# Logturtle_TX_Toplevel.net
KiCad netlist of a schematic drawn in Altium Designer
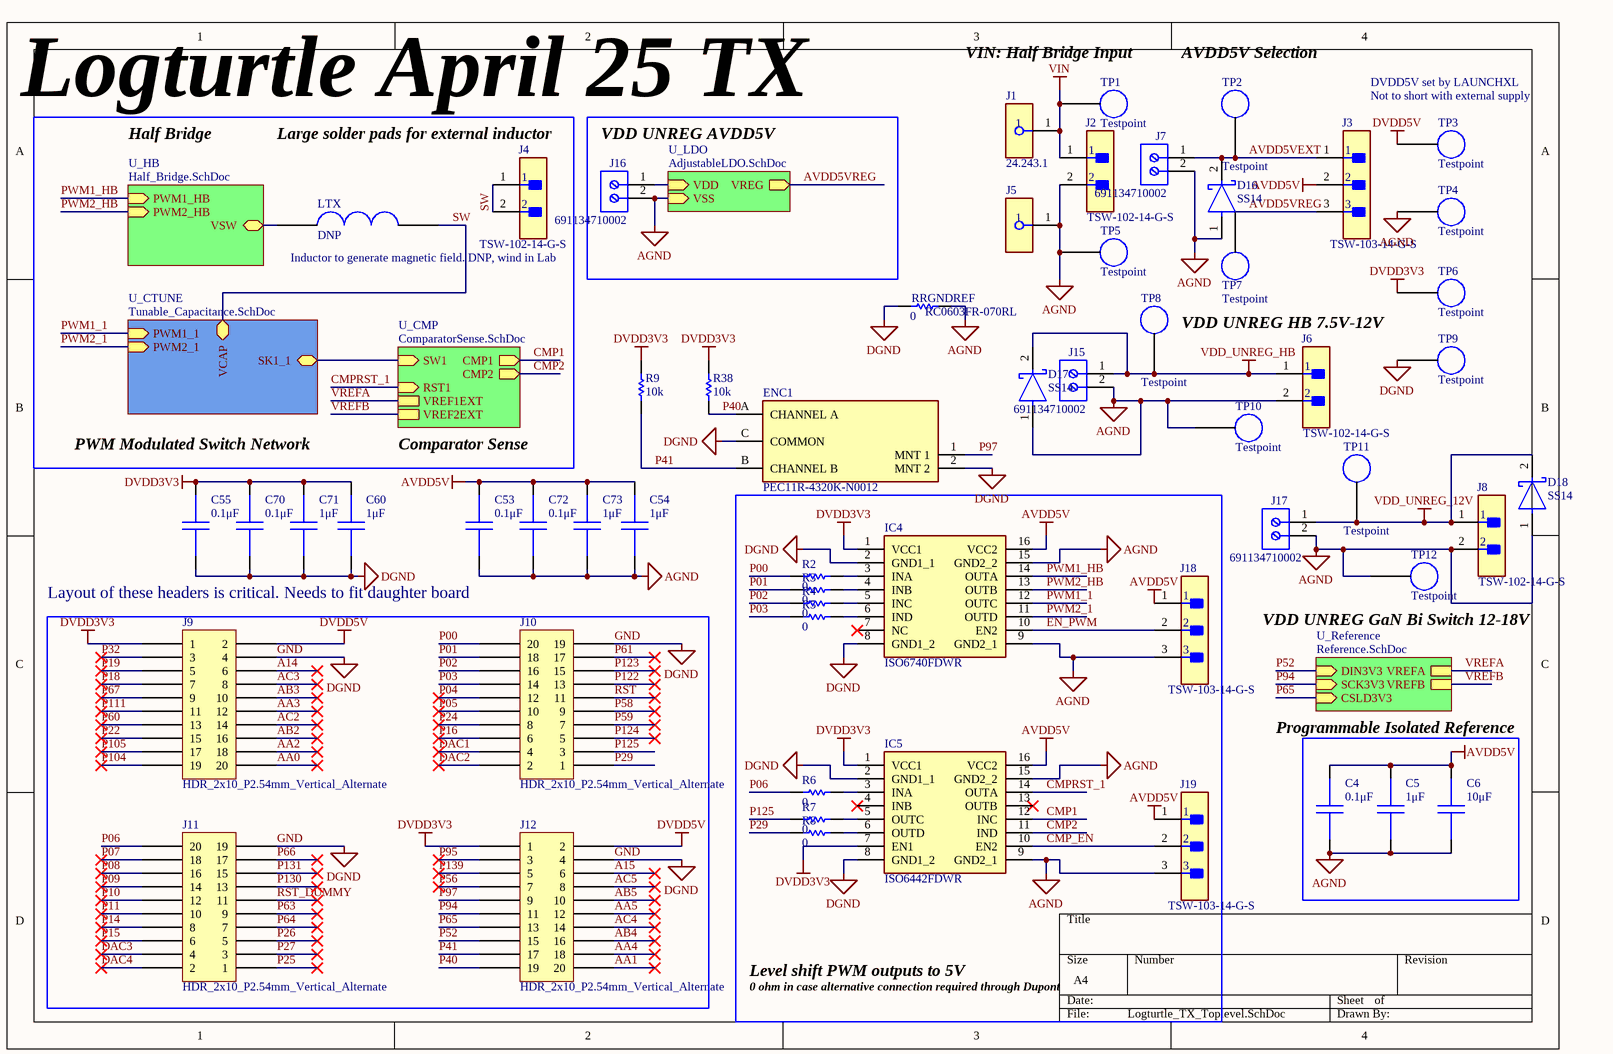
[diagram p0: Logturtle_TX_Toplevel.SchDoc]

(export (version "E")
  (design (tool "Eeschema 10.0.6"))
  (components
    (comp (ref "C4")
      (value "0.1μF")
      (footprint "CAPC1608X90N")
      (fields
        (field (name "MANUFACTURER") "Yageo")
        (field (name "MANUFACTURER PART NUMBER") "CC0603KRX7R7BB104")
      )
      (libsource (lib "LOGTURTLE_APR_25_TX") (part "CC0603KRX7R7BB104"))
    )
    (comp (ref "C5")
      (value "1μF")
      (footprint "CAPC1608X09N")
      (fields
        (field (name "MANUFACTURER") "Yageo")
        (field (name "MANUFACTURER PART NUMBER") "CC0603KRX7R7BB105")
      )
      (libsource (lib "LOGTURTLE_APR_25_TX") (part "CC0603KRX7R7BB105"))
    )
    (comp (ref "C6")
      (value "10μF")
      (footprint "CAPC2012X14N")
      (fields
        (field (name "MANUFACTURER") "Murata")
        (field (name "MANUFACTURER PART NUMBER") "GRM21BZ71E106KE15L")
        (field (name "TOLERANCE") "10%")
      )
      (libsource (lib "LOGTURTLE_APR_25_TX") (part "GRM21BZ71E106KE15L"))
    )
    (comp (ref "C53")
      (value "0.1μF")
      (footprint "CAPC1608X90N")
      (fields
        (field (name "MANUFACTURER") "Yageo")
        (field (name "MANUFACTURER PART NUMBER") "CC0603KRX7R7BB104")
      )
      (libsource (lib "LOGTURTLE_APR_25_TX") (part "CC0603KRX7R7BB104"))
    )
    (comp (ref "C54")
      (value "1μF")
      (footprint "CAPC1608X09N")
      (fields
        (field (name "MANUFACTURER") "Yageo")
        (field (name "MANUFACTURER PART NUMBER") "CC0603KRX7R7BB105")
      )
      (libsource (lib "LOGTURTLE_APR_25_TX") (part "CC0603KRX7R7BB105"))
    )
    (comp (ref "C55")
      (value "0.1μF")
      (footprint "CAPC1608X90N")
      (fields
        (field (name "MANUFACTURER") "Yageo")
        (field (name "MANUFACTURER PART NUMBER") "CC0603KRX7R7BB104")
      )
      (libsource (lib "LOGTURTLE_APR_25_TX") (part "CC0603KRX7R7BB104"))
    )
    (comp (ref "C60")
      (value "1μF")
      (footprint "CAPC1608X09N")
      (fields
        (field (name "MANUFACTURER") "Yageo")
        (field (name "MANUFACTURER PART NUMBER") "CC0603KRX7R7BB105")
      )
      (libsource (lib "LOGTURTLE_APR_25_TX") (part "CC0603KRX7R7BB105"))
    )
    (comp (ref "C70")
      (value "0.1μF")
      (footprint "CAPC1608X90N")
      (fields
        (field (name "MANUFACTURER") "Yageo")
        (field (name "MANUFACTURER PART NUMBER") "CC0603KRX7R7BB104")
      )
      (libsource (lib "LOGTURTLE_APR_25_TX") (part "CC0603KRX7R7BB104"))
    )
    (comp (ref "C71")
      (value "1μF")
      (footprint "CAPC1608X09N")
      (fields
        (field (name "MANUFACTURER") "Yageo")
        (field (name "MANUFACTURER PART NUMBER") "CC0603KRX7R7BB105")
      )
      (libsource (lib "LOGTURTLE_APR_25_TX") (part "CC0603KRX7R7BB105"))
    )
    (comp (ref "C72")
      (value "0.1μF")
      (footprint "CAPC1608X90N")
      (fields
        (field (name "MANUFACTURER") "Yageo")
        (field (name "MANUFACTURER PART NUMBER") "CC0603KRX7R7BB104")
      )
      (libsource (lib "LOGTURTLE_APR_25_TX") (part "CC0603KRX7R7BB104"))
    )
    (comp (ref "C73")
      (value "1μF")
      (footprint "CAPC1608X09N")
      (fields
        (field (name "MANUFACTURER") "Yageo")
        (field (name "MANUFACTURER PART NUMBER") "CC0603KRX7R7BB105")
      )
      (libsource (lib "LOGTURTLE_APR_25_TX") (part "CC0603KRX7R7BB105"))
    )
    (comp (ref "D16")
      (value "SS14")
      (footprint "FP-403AE-MFG")
      (description "DIODE SCHOTTKY 40V 1A SMA")
      (fields
        (field (name "MANUFACTURER") "ON Semiconductor")
        (field (name "OCTOPART") "https://octopart.com/ss14-on+semiconductor-29205033")
      )
      (libsource (lib "Altium Content Vault") (part "360ad2f4ac25a952324d13796385471"))
    )
    (comp (ref "D17")
      (value "SS14")
      (footprint "FP-403AE-MFG")
      (description "DIODE SCHOTTKY 40V 1A SMA")
      (fields
        (field (name "MANUFACTURER") "ON Semiconductor")
        (field (name "OCTOPART") "https://octopart.com/ss14-on+semiconductor-29205033")
      )
      (libsource (lib "Altium Content Vault") (part "360ad2f4ac25a952324d13796385471"))
    )
    (comp (ref "D18")
      (value "SS14")
      (footprint "FP-403AE-MFG")
      (description "DIODE SCHOTTKY 40V 1A SMA")
      (fields
        (field (name "MANUFACTURER") "ON Semiconductor")
        (field (name "OCTOPART") "https://octopart.com/ss14-on+semiconductor-29205033")
      )
      (libsource (lib "Altium Content Vault") (part "360ad2f4ac25a952324d13796385471"))
    )
    (comp (ref "ENC1")
      (value "PEC11R-4320K-N0012")
      (footprint "FP-PEC11R-4320K-N0012-MFG")
      (description "ROTARY ENCODER MECHANICAL 12PPR")
      (libsource (lib "Altium Content Vault") (part "4991351e4cc1ef7df16dc79556137c4"))
    )
    (comp (ref "IC4")
      (value "ISO6740FDWR")
      (footprint "SamacSys:SOIC127P1030X255-16N")
      (description "Texas Instruments ISO6740FDWR")
      (fields (field (name "MANUFACTURER_PART_NUMBER") "ISO6441FDWR"))
      (libsource (lib "LOGTURTLE_APR_25_TX") (part "ISO6440FDWR"))
    )
    (comp (ref "IC5")
      (value "ISO6442FDWR")
      (footprint "SamacSys:SOIC127P1030X255-16N")
      (description "Texas Instruments ISO6742FDWR")
      (fields (field (name "MANUFACTURER_PART_NUMBER") "ISO6441FDWR"))
      (libsource (lib "LOGTURTLE_APR_25_TX") (part "ISO6442FDWR"))
    )
    (comp (ref "J1")
      (value "24.243.1")
      (footprint "FP-24_243_1-MFG")
      (description "Banana Test Connector, 4mm, Socket, PCB Mount, 24 A, 60 VDC, Silver Plated Contacts, Green")
      (libsource (lib "LOGTURTLE_APR_25_TX") (part "CMP-12400-000001-2"))
    )
    (comp (ref "J2")
      (value "TSW-102-14-G-S")
      (footprint "FP-TSW-102-14-G-S-MFG")
      (description "CONN HEADER VERT 2POS 2.54MM")
      (libsource (lib "Altium Content Vault") (part "88c1139f9d239099ffebecbe3f7647a"))
    )
    (comp (ref "J3")
      (value "TSW-103-14-G-S")
      (footprint "FP-TSW-103-14-G-S-MFG")
      (description "CONN HEADER VERT 3POS 2.54MM")
      (libsource (lib "Altium Content Vault") (part "cd3439d6ef35ae5d9b27ec4fdd3e828"))
    )
    (comp (ref "J4")
      (value "TSW-102-14-G-S")
      (footprint "FP-TSW-102-14-G-S-MFG")
      (description "CONN HEADER VERT 2POS 2.54MM")
      (libsource (lib "Altium Content Vault") (part "88c1139f9d239099ffebecbe3f7647a"))
    )
    (comp (ref "J5")
      (value "~")
      (footprint "FP-24_243_2-MFG")
      (description "RECEPTACLE, 20A, 4MM, PCB, SOLDER, BLACK")
      (libsource (lib "LOGTURTLE_APR_25_TX") (part "c5c826e0c4b67fe3b42ef77f2d4decc"))
    )
    (comp (ref "J6")
      (value "TSW-102-14-G-S")
      (footprint "FP-TSW-102-14-G-S-MFG")
      (description "CONN HEADER VERT 2POS 2.54MM")
      (libsource (lib "Altium Content Vault") (part "88c1139f9d239099ffebecbe3f7647a"))
    )
    (comp (ref "J7")
      (value "691134710002")
      (footprint "691134710002")
      (description "Wire-To-Board Terminal Block, 5mm Pitch, Horizontal, Screw, 2 Poles")
      (libsource (lib "Altium Content Vault") (part "TBL - 1R - 02P - Screw"))
    )
    (comp (ref "J8")
      (value "TSW-102-14-G-S")
      (footprint "FP-TSW-102-14-G-S-MFG")
      (description "CONN HEADER VERT 2POS 2.54MM")
      (libsource (lib "Altium Content Vault") (part "88c1139f9d239099ffebecbe3f7647a"))
    )
    (comp (ref "J9")
      (value "HDR_2x10_P2.54mm_Vertical_Alternate")
      (footprint "HDR_2x10_P2.54mm_Vertical - Alternate")
      (libsource (lib "") (part "HDR_2x10_P2.54mm_Vertical_Alternate_1"))
    )
    (comp (ref "J10")
      (value "HDR_2x10_P2.54mm_Vertical_Alternate")
      (footprint "HDR_2x10_P2.54mm_Vertical - Alternate")
      (libsource (lib "LOGTURTLE_APR_25_TX") (part "HDR_2x10_P2.54mm_Vertical_Alternate"))
    )
    (comp (ref "J11")
      (value "HDR_2x10_P2.54mm_Vertical_Alternate")
      (footprint "HDR_2x10_P2.54mm_Vertical - Alternate")
      (libsource (lib "LOGTURTLE_APR_25_TX") (part "HDR_2x10_P2.54mm_Vertical_Alternate"))
    )
    (comp (ref "J12")
      (value "HDR_2x10_P2.54mm_Vertical_Alternate")
      (footprint "HDR_2x10_P2.54mm_Vertical - Alternate")
      (libsource (lib "") (part "HDR_2x10_P2.54mm_Vertical_Alternate_1"))
    )
    (comp (ref "J15")
      (value "691134710002")
      (footprint "691134710002")
      (description "Wire-To-Board Terminal Block, 5mm Pitch, Horizontal, Screw, 2 Poles")
      (libsource (lib "Altium Content Vault") (part "TBL - 1R - 02P - Screw"))
    )
    (comp (ref "J16")
      (value "691134710002")
      (footprint "691134710002")
      (description "Wire-To-Board Terminal Block, 5mm Pitch, Horizontal, Screw, 2 Poles")
      (libsource (lib "Altium Content Vault") (part "TBL - 1R - 02P - Screw"))
    )
    (comp (ref "J17")
      (value "691134710002")
      (footprint "691134710002")
      (description "Wire-To-Board Terminal Block, 5mm Pitch, Horizontal, Screw, 2 Poles")
      (libsource (lib "Altium Content Vault") (part "TBL - 1R - 02P - Screw"))
    )
    (comp (ref "J18")
      (value "TSW-103-14-G-S")
      (footprint "FP-TSW-103-14-G-S-MFG")
      (description "CONN HEADER VERT 3POS 2.54MM")
      (libsource (lib "Altium Content Vault") (part "cd3439d6ef35ae5d9b27ec4fdd3e828"))
    )
    (comp (ref "J19")
      (value "TSW-103-14-G-S")
      (footprint "FP-TSW-103-14-G-S-MFG")
      (description "CONN HEADER VERT 3POS 2.54MM")
      (libsource (lib "Altium Content Vault") (part "cd3439d6ef35ae5d9b27ec4fdd3e828"))
    )
    (comp (ref "LTX")
      (value "DNP")
      (footprint "InductorTerminals")
      (libsource (lib "LOGTURTLE_APR_25_TX") (part "InductorTX"))
    )
    (comp (ref "R2")
      (value "0")
      (footprint "RESC1608X55N")
      (description "Resistor, 0 Ohms Jumper 0.1W, 1/10W Chip Resistor 0603 (1608 Metric) Moisture Resistant Thick Film")
      (fields
        (field (name "MANUFACTURER_PART_NUMBER") "RC0603FR-070RL")
        (field (name "MOUSER PART NUMBER") "603-RC0603FR-070RL")
      )
      (libsource (lib "LOGTURTLE_APR_25_TX") (part "RC0603FR-070RL"))
    )
    (comp (ref "R3")
      (value "0")
      (footprint "RESC1608X55N")
      (description "Resistor, 0 Ohms Jumper 0.1W, 1/10W Chip Resistor 0603 (1608 Metric) Moisture Resistant Thick Film")
      (fields
        (field (name "MANUFACTURER_PART_NUMBER") "RC0603FR-070RL")
        (field (name "MOUSER PART NUMBER") "603-RC0603FR-070RL")
      )
      (libsource (lib "LOGTURTLE_APR_25_TX") (part "RC0603FR-070RL"))
    )
    (comp (ref "R4")
      (value "0")
      (footprint "RESC1608X55N")
      (description "Resistor, 0 Ohms Jumper 0.1W, 1/10W Chip Resistor 0603 (1608 Metric) Moisture Resistant Thick Film")
      (fields
        (field (name "MANUFACTURER_PART_NUMBER") "RC0603FR-070RL")
        (field (name "MOUSER PART NUMBER") "603-RC0603FR-070RL")
      )
      (libsource (lib "LOGTURTLE_APR_25_TX") (part "RC0603FR-070RL"))
    )
    (comp (ref "R5")
      (value "0")
      (footprint "RESC1608X55N")
      (description "Resistor, 0 Ohms Jumper 0.1W, 1/10W Chip Resistor 0603 (1608 Metric) Moisture Resistant Thick Film")
      (fields
        (field (name "MANUFACTURER_PART_NUMBER") "RC0603FR-070RL")
        (field (name "MOUSER PART NUMBER") "603-RC0603FR-070RL")
      )
      (libsource (lib "LOGTURTLE_APR_25_TX") (part "RC0603FR-070RL"))
    )
    (comp (ref "R6")
      (value "0")
      (footprint "RESC1608X55N")
      (description "Resistor, 0 Ohms Jumper 0.1W, 1/10W Chip Resistor 0603 (1608 Metric) Moisture Resistant Thick Film")
      (fields
        (field (name "MANUFACTURER_PART_NUMBER") "RC0603FR-070RL")
        (field (name "MOUSER PART NUMBER") "603-RC0603FR-070RL")
      )
      (libsource (lib "LOGTURTLE_APR_25_TX") (part "RC0603FR-070RL"))
    )
    (comp (ref "R7")
      (value "0")
      (footprint "RESC1608X55N")
      (description "Resistor, 0 Ohms Jumper 0.1W, 1/10W Chip Resistor 0603 (1608 Metric) Moisture Resistant Thick Film")
      (fields
        (field (name "MANUFACTURER_PART_NUMBER") "RC0603FR-070RL")
        (field (name "MOUSER PART NUMBER") "603-RC0603FR-070RL")
      )
      (libsource (lib "LOGTURTLE_APR_25_TX") (part "RC0603FR-070RL"))
    )
    (comp (ref "R8")
      (value "0")
      (footprint "RESC1608X55N")
      (description "Resistor, 0 Ohms Jumper 0.1W, 1/10W Chip Resistor 0603 (1608 Metric) Moisture Resistant Thick Film")
      (fields
        (field (name "MANUFACTURER_PART_NUMBER") "RC0603FR-070RL")
        (field (name "MOUSER PART NUMBER") "603-RC0603FR-070RL")
      )
      (libsource (lib "LOGTURTLE_APR_25_TX") (part "RC0603FR-070RL"))
    )
    (comp (ref "R9")
      (value "10k")
      (footprint "RESC1608X55N")
      (description "Resistor, 10 kOhms ±1% 0.1W, 1/10W Chip Resistor 0603 (1608 Metric) Moisture Resistant Thick Film")
      (fields (field (name "MANUFACTURER_PART_NUMBER") "RC0603FR0710KL"))
      (libsource (lib "LOGTURTLE_APR_25_TX") (part "RC0603FR0710KL"))
    )
    (comp (ref "R38")
      (value "10k")
      (footprint "RESC1608X55N")
      (description "Resistor, 10 kOhms ±1% 0.1W, 1/10W Chip Resistor 0603 (1608 Metric) Moisture Resistant Thick Film")
      (fields (field (name "MANUFACTURER_PART_NUMBER") "RC0603FR0710KL"))
      (libsource (lib "LOGTURTLE_APR_25_TX") (part "RC0603FR0710KL"))
    )
    (comp (ref "RRGNDREF")
      (value "RC0603FR-070RL")
      (footprint "RESC1608X55N")
      (description "Resistor, 0 Ohms Jumper 0.1W, 1/10W Chip Resistor 0603 (1608 Metric) Moisture Resistant Thick Film")
      (fields (field (name "ALTIUM_VALUE") "0") (field (name "MOUSER PART NUMBER") "603-RC0603FR-070RL"))
      (libsource (lib "LOGTURTLE_APR_25_TX") (part "RC0603FR-070RL"))
    )
    (comp (ref "TP1")
      (value "Testpoint")
      (footprint "TP_5006")
      (libsource (lib "LOGTURTLE_APR_25_TX") (part "Testpoint"))
    )
    (comp (ref "TP2")
      (value "Testpoint")
      (footprint "TP_5006")
      (libsource (lib "LOGTURTLE_APR_25_TX") (part "Testpoint"))
    )
    (comp (ref "TP3")
      (value "Testpoint")
      (footprint "TP_5006")
      (libsource (lib "LOGTURTLE_APR_25_TX") (part "Testpoint"))
    )
    (comp (ref "TP4")
      (value "Testpoint")
      (footprint "TP_5006")
      (libsource (lib "LOGTURTLE_APR_25_TX") (part "Testpoint"))
    )
    (comp (ref "TP5")
      (value "Testpoint")
      (footprint "TP_5006")
      (libsource (lib "LOGTURTLE_APR_25_TX") (part "Testpoint"))
    )
    (comp (ref "TP6")
      (value "Testpoint")
      (footprint "TP_5006")
      (libsource (lib "LOGTURTLE_APR_25_TX") (part "Testpoint"))
    )
    (comp (ref "TP7")
      (value "Testpoint")
      (footprint "TP_5006")
      (libsource (lib "LOGTURTLE_APR_25_TX") (part "Testpoint"))
    )
    (comp (ref "TP8")
      (value "Testpoint")
      (footprint "TP_5006")
      (libsource (lib "LOGTURTLE_APR_25_TX") (part "Testpoint"))
    )
    (comp (ref "TP9")
      (value "Testpoint")
      (footprint "TP_5006")
      (libsource (lib "LOGTURTLE_APR_25_TX") (part "Testpoint"))
    )
    (comp (ref "TP10")
      (value "Testpoint")
      (footprint "TP_5006")
      (libsource (lib "LOGTURTLE_APR_25_TX") (part "Testpoint"))
    )
    (comp (ref "TP11")
      (value "Testpoint")
      (footprint "TP_5006")
      (libsource (lib "LOGTURTLE_APR_25_TX") (part "Testpoint"))
    )
    (comp (ref "TP12")
      (value "Testpoint")
      (footprint "TP_5006")
      (libsource (lib "LOGTURTLE_APR_25_TX") (part "Testpoint"))
    )
  )
  (nets
    (net (code "1") (name "/A14") (class "Default")
      (node (ref "J9") (pin "6") (pinfunction "6_6") (pintype "passive+no_connect"))
    )
    (net (code "2") (name "/A15") (class "Default")
      (node (ref "J12") (pin "6") (pinfunction "6_6") (pintype "passive+no_connect"))
    )
    (net (code "3") (name "/AA0") (class "Default")
      (node (ref "J9") (pin "20") (pinfunction "20_20") (pintype "passive+no_connect"))
    )
    (net (code "4") (name "/AA1") (class "Default")
      (node (ref "J12") (pin "20") (pinfunction "20_20") (pintype "passive+no_connect"))
    )
    (net (code "5") (name "/AA2") (class "Default")
      (node (ref "J9") (pin "18") (pinfunction "18_18") (pintype "passive+no_connect"))
    )
    (net (code "6") (name "/AA3") (class "Default")
      (node (ref "J9") (pin "12") (pinfunction "12_12") (pintype "passive+no_connect"))
    )
    (net (code "7") (name "/AA4") (class "Default")
      (node (ref "J12") (pin "18") (pinfunction "18_18") (pintype "passive+no_connect"))
    )
    (net (code "8") (name "/AA5") (class "Default")
      (node (ref "J12") (pin "12") (pinfunction "12_12") (pintype "passive+no_connect"))
    )
    (net (code "9") (name "/AB2") (class "Default")
      (node (ref "J9") (pin "16") (pinfunction "16_16") (pintype "passive+no_connect"))
    )
    (net (code "10") (name "/AB3") (class "Default")
      (node (ref "J9") (pin "10") (pinfunction "10_10") (pintype "passive+no_connect"))
    )
    (net (code "11") (name "/AB4") (class "Default")
      (node (ref "J12") (pin "16") (pinfunction "16_16") (pintype "passive+no_connect"))
    )
    (net (code "12") (name "/AB5") (class "Default")
      (node (ref "J12") (pin "10") (pinfunction "10_10") (pintype "passive+no_connect"))
    )
    (net (code "13") (name "/AC2") (class "Default")
      (node (ref "J9") (pin "14") (pinfunction "14_14") (pintype "passive+no_connect"))
    )
    (net (code "14") (name "/AC3") (class "Default")
      (node (ref "J9") (pin "8") (pinfunction "8_8") (pintype "passive+no_connect"))
    )
    (net (code "15") (name "/AC4") (class "Default")
      (node (ref "J12") (pin "14") (pinfunction "14_14") (pintype "passive+no_connect"))
    )
    (net (code "16") (name "/AC5") (class "Default")
      (node (ref "J12") (pin "8") (pinfunction "8_8") (pintype "passive+no_connect"))
    )
    (net (code "17") (name "/AVDD5VEXT") (class "Default")
      (node (ref "D16") (pin "2") (pinfunction "C_2") (pintype "passive"))
      (node (ref "J3") (pin "1") (pinfunction "1_1") (pintype "passive"))
      (node (ref "J7") (pin "1") (pinfunction "1_1") (pintype "passive"))
      (node (ref "TP2") (pin "1") (pinfunction "1_1") (pintype "passive"))
    )
    (net (code "18") (name "/AVDD5VREG") (class "Default")
      (node (ref "J3") (pin "3") (pinfunction "3_3") (pintype "passive"))
      (node (ref "TP7") (pin "1") (pinfunction "1_1") (pintype "passive"))
    )
    (net (code "19") (name "/CMP1") (class "Default")
      (node (ref "IC5") (pin "12") (pinfunction "INC_12") (pintype "passive"))
    )
    (net (code "20") (name "/CMP2") (class "Default")
      (node (ref "IC5") (pin "11") (pinfunction "IND_11") (pintype "passive"))
    )
    (net (code "21") (name "/CMPRST_1") (class "Default")
      (node (ref "IC5") (pin "14") (pinfunction "OUTA_14") (pintype "passive"))
    )
    (net (code "22") (name "/CMP_EN") (class "Default")
      (node (ref "IC5") (pin "10") (pinfunction "EN2_10") (pintype "passive"))
      (node (ref "J19") (pin "2") (pinfunction "2_2") (pintype "passive"))
    )
    (net (code "23") (name "/DAC1") (class "Default")
      (node (ref "J10") (pin "4") (pinfunction "4_4") (pintype "passive+no_connect"))
    )
    (net (code "24") (name "/DAC2") (class "Default")
      (node (ref "J10") (pin "2") (pinfunction "2_2") (pintype "passive+no_connect"))
    )
    (net (code "25") (name "/DAC3") (class "Default")
      (node (ref "J11") (pin "4") (pinfunction "4_4") (pintype "passive+no_connect"))
    )
    (net (code "26") (name "/DAC4") (class "Default")
      (node (ref "J11") (pin "2") (pinfunction "2_2") (pintype "passive+no_connect"))
    )
    (net (code "27") (name "/EN_PWM") (class "Default")
      (node (ref "IC4") (pin "10") (pinfunction "EN2_10") (pintype "passive"))
      (node (ref "J18") (pin "2") (pinfunction "2_2") (pintype "passive"))
    )
    (net (code "28") (name "/P00") (class "Default")
      (node (ref "J10") (pin "20") (pinfunction "20_20") (pintype "passive"))
      (node (ref "R2") (pin "1") (pinfunction "1_1") (pintype "passive"))
    )
    (net (code "29") (name "/P01") (class "Default")
      (node (ref "J10") (pin "18") (pinfunction "18_18") (pintype "passive"))
      (node (ref "R3") (pin "1") (pinfunction "1_1") (pintype "passive"))
    )
    (net (code "30") (name "/P02") (class "Default")
      (node (ref "J10") (pin "16") (pinfunction "16_16") (pintype "passive"))
      (node (ref "R4") (pin "1") (pinfunction "1_1") (pintype "passive"))
    )
    (net (code "31") (name "/P03") (class "Default")
      (node (ref "J10") (pin "14") (pinfunction "14_14") (pintype "passive"))
      (node (ref "R5") (pin "1") (pinfunction "1_1") (pintype "passive"))
    )
    (net (code "32") (name "/P04") (class "Default")
      (node (ref "J10") (pin "12") (pinfunction "12_12") (pintype "passive+no_connect"))
    )
    (net (code "33") (name "/P05") (class "Default")
      (node (ref "J10") (pin "10") (pinfunction "10_10") (pintype "passive+no_connect"))
    )
    (net (code "34") (name "/P06") (class "Default")
      (node (ref "J11") (pin "20") (pinfunction "20_20") (pintype "passive"))
      (node (ref "R6") (pin "1") (pinfunction "1_1") (pintype "passive"))
    )
    (net (code "35") (name "/P07") (class "Default")
      (node (ref "J11") (pin "18") (pinfunction "18_18") (pintype "passive+no_connect"))
    )
    (net (code "36") (name "/P08") (class "Default")
      (node (ref "J11") (pin "16") (pinfunction "16_16") (pintype "passive+no_connect"))
    )
    (net (code "37") (name "/P09") (class "Default")
      (node (ref "J11") (pin "14") (pinfunction "14_14") (pintype "passive+no_connect"))
    )
    (net (code "38") (name "/P10") (class "Default")
      (node (ref "J11") (pin "12") (pinfunction "12_12") (pintype "passive+no_connect"))
    )
    (net (code "39") (name "/P11") (class "Default")
      (node (ref "J11") (pin "10") (pinfunction "10_10") (pintype "passive+no_connect"))
    )
    (net (code "40") (name "/P14") (class "Default")
      (node (ref "J11") (pin "8") (pinfunction "8_8") (pintype "passive+no_connect"))
    )
    (net (code "41") (name "/P15") (class "Default")
      (node (ref "J11") (pin "6") (pinfunction "6_6") (pintype "passive+no_connect"))
    )
    (net (code "42") (name "/P16") (class "Default")
      (node (ref "J10") (pin "6") (pinfunction "6_6") (pintype "passive+no_connect"))
    )
    (net (code "43") (name "/P18") (class "Default")
      (node (ref "J9") (pin "7") (pinfunction "7_7") (pintype "passive+no_connect"))
    )
    (net (code "44") (name "/P19") (class "Default")
      (node (ref "J9") (pin "5") (pinfunction "5_5") (pintype "passive+no_connect"))
    )
    (net (code "45") (name "/P22") (class "Default")
      (node (ref "J9") (pin "15") (pinfunction "15_15") (pintype "passive+no_connect"))
    )
    (net (code "46") (name "/P24") (class "Default")
      (node (ref "J10") (pin "8") (pinfunction "8_8") (pintype "passive+no_connect"))
    )
    (net (code "47") (name "/P25") (class "Default")
      (node (ref "J11") (pin "1") (pinfunction "1_1") (pintype "passive+no_connect"))
    )
    (net (code "48") (name "/P26") (class "Default")
      (node (ref "J11") (pin "5") (pinfunction "5_5") (pintype "passive+no_connect"))
    )
    (net (code "49") (name "/P27") (class "Default")
      (node (ref "J11") (pin "3") (pinfunction "3_3") (pintype "passive+no_connect"))
    )
    (net (code "50") (name "/P29") (class "Default")
      (node (ref "J10") (pin "1") (pinfunction "1_1") (pintype "passive"))
      (node (ref "R8") (pin "1") (pinfunction "1_1") (pintype "passive"))
    )
    (net (code "51") (name "/P32") (class "Default")
      (node (ref "J9") (pin "3") (pinfunction "3_3") (pintype "passive+no_connect"))
    )
    (net (code "52") (name "/P40") (class "Default")
      (node (ref "ENC1") (pin "A") (pinfunction "CHANNEL_A_A") (pintype "passive"))
      (node (ref "J12") (pin "19") (pinfunction "19_19") (pintype "passive"))
      (node (ref "R38") (pin "1") (pinfunction "1_1") (pintype "passive"))
    )
    (net (code "53") (name "/P41") (class "Default")
      (node (ref "ENC1") (pin "B") (pinfunction "CHANNEL_B_B") (pintype "passive"))
      (node (ref "J12") (pin "17") (pinfunction "17_17") (pintype "passive"))
      (node (ref "R9") (pin "1") (pinfunction "1_1") (pintype "passive"))
    )
    (net (code "54") (name "/P52") (class "Default")
      (node (ref "J12") (pin "15") (pinfunction "15_15") (pintype "passive"))
    )
    (net (code "55") (name "/P56") (class "Default")
      (node (ref "J12") (pin "7") (pinfunction "7_7") (pintype "passive+no_connect"))
    )
    (net (code "56") (name "/P58") (class "Default")
      (node (ref "J10") (pin "9") (pinfunction "9_9") (pintype "passive+no_connect"))
    )
    (net (code "57") (name "/P59") (class "Default")
      (node (ref "J10") (pin "7") (pinfunction "7_7") (pintype "passive+no_connect"))
    )
    (net (code "58") (name "/P60") (class "Default")
      (node (ref "J9") (pin "13") (pinfunction "13_13") (pintype "passive+no_connect"))
    )
    (net (code "59") (name "/P61") (class "Default")
      (node (ref "J10") (pin "17") (pinfunction "17_17") (pintype "passive+no_connect"))
    )
    (net (code "60") (name "/P63") (class "Default")
      (node (ref "J11") (pin "9") (pinfunction "9_9") (pintype "passive+no_connect"))
    )
    (net (code "61") (name "/P64") (class "Default")
      (node (ref "J11") (pin "7") (pinfunction "7_7") (pintype "passive+no_connect"))
    )
    (net (code "62") (name "/P65") (class "Default")
      (node (ref "J12") (pin "13") (pinfunction "13_13") (pintype "passive"))
    )
    (net (code "63") (name "/P66") (class "Default")
      (node (ref "J11") (pin "17") (pinfunction "17_17") (pintype "passive+no_connect"))
    )
    (net (code "64") (name "/P67") (class "Default")
      (node (ref "J9") (pin "9") (pinfunction "9_9") (pintype "passive+no_connect"))
    )
    (net (code "65") (name "/P94") (class "Default")
      (node (ref "J12") (pin "11") (pinfunction "11_11") (pintype "passive"))
    )
    (net (code "66") (name "/P95") (class "Default")
      (node (ref "J12") (pin "3") (pinfunction "3_3") (pintype "passive+no_connect"))
    )
    (net (code "67") (name "/P97") (class "Default")
      (node (ref "ENC1") (pin "1") (pinfunction "MNT_1_1") (pintype "passive"))
      (node (ref "J12") (pin "9") (pinfunction "9_9") (pintype "passive"))
    )
    (net (code "68") (name "/P104") (class "Default")
      (node (ref "J9") (pin "19") (pinfunction "19_19") (pintype "passive+no_connect"))
    )
    (net (code "69") (name "/P105") (class "Default")
      (node (ref "J9") (pin "17") (pinfunction "17_17") (pintype "passive+no_connect"))
    )
    (net (code "70") (name "/P111") (class "Default")
      (node (ref "J9") (pin "11") (pinfunction "11_11") (pintype "passive+no_connect"))
    )
    (net (code "71") (name "/P122") (class "Default")
      (node (ref "J10") (pin "13") (pinfunction "13_13") (pintype "passive+no_connect"))
    )
    (net (code "72") (name "/P123") (class "Default")
      (node (ref "J10") (pin "15") (pinfunction "15_15") (pintype "passive+no_connect"))
    )
    (net (code "73") (name "/P124") (class "Default")
      (node (ref "J10") (pin "5") (pinfunction "5_5") (pintype "passive+no_connect"))
    )
    (net (code "74") (name "/P125") (class "Default")
      (node (ref "J10") (pin "3") (pinfunction "3_3") (pintype "passive"))
      (node (ref "R7") (pin "1") (pinfunction "1_1") (pintype "passive"))
    )
    (net (code "75") (name "/P130") (class "Default")
      (node (ref "J11") (pin "13") (pinfunction "13_13") (pintype "passive+no_connect"))
    )
    (net (code "76") (name "/P131") (class "Default")
      (node (ref "J11") (pin "15") (pinfunction "15_15") (pintype "passive+no_connect"))
    )
    (net (code "77") (name "/P139") (class "Default")
      (node (ref "J12") (pin "5") (pinfunction "5_5") (pintype "passive+no_connect"))
    )
    (net (code "78") (name "/PWM1_1") (class "Default")
      (node (ref "IC4") (pin "12") (pinfunction "OUTC_12") (pintype "passive"))
    )
    (net (code "79") (name "/PWM1_HB") (class "Default")
      (node (ref "IC4") (pin "14") (pinfunction "OUTA_14") (pintype "passive"))
    )
    (net (code "80") (name "/PWM2_1") (class "Default")
      (node (ref "IC4") (pin "11") (pinfunction "OUTD_11") (pintype "passive"))
    )
    (net (code "81") (name "/PWM2_HB") (class "Default")
      (node (ref "IC4") (pin "13") (pinfunction "OUTB_13") (pintype "passive"))
    )
    (net (code "82") (name "/RST") (class "Default")
      (node (ref "J10") (pin "11") (pinfunction "11_11") (pintype "passive+no_connect"))
    )
    (net (code "83") (name "/RST_DUMMY") (class "Default")
      (node (ref "J11") (pin "11") (pinfunction "11_11") (pintype "passive+no_connect"))
    )
    (net (code "85") (name "/SW") (class "Default")
      (node (ref "J4") (pin "1") (pinfunction "1_1") (pintype "passive"))
      (node (ref "J4") (pin "2") (pinfunction "2_2") (pintype "passive"))
      (node (ref "LTX") (pin "2") (pinfunction "2_2") (pintype "passive"))
    )
    (net (code "86") (name "/VDD") (class "Default")
      (node (ref "J16") (pin "1") (pinfunction "1_1") (pintype "passive"))
    )
    (net (code "89") (name "/VSW") (class "Default")
      (node (ref "LTX") (pin "1") (pinfunction "1_1") (pintype "passive"))
    )
    (net (code "90") (name "AGND") (class "Default")
      (node (ref "C4") (pin "1") (pinfunction "1_1") (pintype "passive"))
      (node (ref "C5") (pin "1") (pinfunction "1_1") (pintype "passive"))
      (node (ref "C53") (pin "1") (pinfunction "1_1") (pintype "passive"))
      (node (ref "C54") (pin "1") (pinfunction "1_1") (pintype "passive"))
      (node (ref "C6") (pin "1") (pinfunction "1_1") (pintype "passive"))
      (node (ref "C72") (pin "1") (pinfunction "1_1") (pintype "passive"))
      (node (ref "C73") (pin "1") (pinfunction "1_1") (pintype "passive"))
      (node (ref "D16") (pin "1") (pinfunction "A_1") (pintype "passive"))
      (node (ref "D17") (pin "1") (pinfunction "A_1") (pintype "passive"))
      (node (ref "D18") (pin "1") (pinfunction "A_1") (pintype "passive"))
      (node (ref "IC4") (pin "15") (pinfunction "GND2_2_15") (pintype "passive"))
      (node (ref "IC4") (pin "9") (pinfunction "GND2_1_9") (pintype "passive"))
      (node (ref "IC5") (pin "15") (pinfunction "GND2_2_15") (pintype "passive"))
      (node (ref "IC5") (pin "9") (pinfunction "GND2_1_9") (pintype "passive"))
      (node (ref "J15") (pin "2") (pinfunction "2_2") (pintype "passive"))
      (node (ref "J16") (pin "2") (pinfunction "2_2") (pintype "passive"))
      (node (ref "J17") (pin "2") (pinfunction "2_2") (pintype "passive"))
      (node (ref "J18") (pin "3") (pinfunction "3_3") (pintype "passive"))
      (node (ref "J19") (pin "3") (pinfunction "3_3") (pintype "passive"))
      (node (ref "J2") (pin "2") (pinfunction "2_2") (pintype "passive"))
      (node (ref "J5") (pin "1") (pinfunction "1_1") (pintype "passive"))
      (node (ref "J6") (pin "2") (pinfunction "2_2") (pintype "passive"))
      (node (ref "J7") (pin "2") (pinfunction "2_2") (pintype "passive"))
      (node (ref "J8") (pin "2") (pinfunction "2_2") (pintype "passive"))
      (node (ref "RRGNDREF") (pin "1") (pinfunction "1_1") (pintype "passive"))
      (node (ref "TP10") (pin "1") (pinfunction "1_1") (pintype "passive"))
      (node (ref "TP12") (pin "1") (pinfunction "1_1") (pintype "passive"))
      (node (ref "TP4") (pin "1") (pinfunction "1_1") (pintype "passive"))
      (node (ref "TP5") (pin "1") (pinfunction "1_1") (pintype "passive"))
    )
    (net (code "91") (name "AVDD5V") (class "Default")
      (node (ref "C4") (pin "2") (pinfunction "2_2") (pintype "passive"))
      (node (ref "C5") (pin "2") (pinfunction "2_2") (pintype "passive"))
      (node (ref "C53") (pin "2") (pinfunction "2_2") (pintype "passive"))
      (node (ref "C54") (pin "2") (pinfunction "2_2") (pintype "passive"))
      (node (ref "C6") (pin "2") (pinfunction "2_2") (pintype "passive"))
      (node (ref "C72") (pin "2") (pinfunction "2_2") (pintype "passive"))
      (node (ref "C73") (pin "2") (pinfunction "2_2") (pintype "passive"))
      (node (ref "IC4") (pin "16") (pinfunction "VCC2_16") (pintype "passive"))
      (node (ref "IC5") (pin "16") (pinfunction "VCC2_16") (pintype "passive"))
      (node (ref "J18") (pin "1") (pinfunction "1_1") (pintype "passive"))
      (node (ref "J19") (pin "1") (pinfunction "1_1") (pintype "passive"))
      (node (ref "J3") (pin "2") (pinfunction "2_2") (pintype "passive"))
    )
    (net (code "92") (name "DGND") (class "Default")
      (node (ref "C55") (pin "1") (pinfunction "1_1") (pintype "passive"))
      (node (ref "C60") (pin "1") (pinfunction "1_1") (pintype "passive"))
      (node (ref "C70") (pin "1") (pinfunction "1_1") (pintype "passive"))
      (node (ref "C71") (pin "1") (pinfunction "1_1") (pintype "passive"))
      (node (ref "ENC1") (pin "2") (pinfunction "MNT_2_2") (pintype "passive"))
      (node (ref "ENC1") (pin "C") (pinfunction "COMMON_C") (pintype "passive"))
      (node (ref "IC4") (pin "2") (pinfunction "GND1_1_2") (pintype "passive"))
      (node (ref "IC4") (pin "8") (pinfunction "GND1_2_8") (pintype "passive"))
      (node (ref "IC5") (pin "2") (pinfunction "GND1_1_2") (pintype "passive"))
      (node (ref "IC5") (pin "8") (pinfunction "GND1_2_8") (pintype "passive"))
      (node (ref "J10") (pin "19") (pinfunction "19_19") (pintype "passive"))
      (node (ref "J11") (pin "19") (pinfunction "19_19") (pintype "passive"))
      (node (ref "J12") (pin "4") (pinfunction "4_4") (pintype "passive"))
      (node (ref "J9") (pin "4") (pinfunction "4_4") (pintype "passive"))
      (node (ref "RRGNDREF") (pin "2") (pinfunction "2_2") (pintype "passive"))
      (node (ref "TP9") (pin "1") (pinfunction "1_1") (pintype "passive"))
    )
    (net (code "93") (name "DVDD3V3") (class "Default")
      (node (ref "C55") (pin "2") (pinfunction "2_2") (pintype "passive"))
      (node (ref "C60") (pin "2") (pinfunction "2_2") (pintype "passive"))
      (node (ref "C70") (pin "2") (pinfunction "2_2") (pintype "passive"))
      (node (ref "C71") (pin "2") (pinfunction "2_2") (pintype "passive"))
      (node (ref "IC4") (pin "1") (pinfunction "VCC1_1") (pintype "passive"))
      (node (ref "IC5") (pin "1") (pinfunction "VCC1_1") (pintype "passive"))
      (node (ref "IC5") (pin "7") (pinfunction "EN1_7") (pintype "passive"))
      (node (ref "J12") (pin "1") (pinfunction "1_1") (pintype "passive"))
      (node (ref "J9") (pin "1") (pinfunction "1_1") (pintype "passive"))
      (node (ref "R38") (pin "2") (pinfunction "2_2") (pintype "passive"))
      (node (ref "R9") (pin "2") (pinfunction "2_2") (pintype "passive"))
      (node (ref "TP6") (pin "1") (pinfunction "1_1") (pintype "passive"))
    )
    (net (code "94") (name "DVDD5V") (class "Default")
      (node (ref "J12") (pin "2") (pinfunction "2_2") (pintype "passive"))
      (node (ref "J9") (pin "2") (pinfunction "2_2") (pintype "passive"))
      (node (ref "TP3") (pin "1") (pinfunction "1_1") (pintype "passive"))
    )
    (net (code "95") (name "Net-(IC4-INA)") (class "Default")
      (node (ref "IC4") (pin "3") (pinfunction "INA_3") (pintype "passive"))
      (node (ref "R2") (pin "2") (pinfunction "2_2") (pintype "passive"))
    )
    (net (code "96") (name "Net-(IC4-INB)") (class "Default")
      (node (ref "IC4") (pin "4") (pinfunction "INB_4") (pintype "passive"))
      (node (ref "R3") (pin "2") (pinfunction "2_2") (pintype "passive"))
    )
    (net (code "97") (name "Net-(IC4-INC)") (class "Default")
      (node (ref "IC4") (pin "5") (pinfunction "INC_5") (pintype "passive"))
      (node (ref "R4") (pin "2") (pinfunction "2_2") (pintype "passive"))
    )
    (net (code "98") (name "Net-(IC4-IND)") (class "Default")
      (node (ref "IC4") (pin "6") (pinfunction "IND_6") (pintype "passive"))
      (node (ref "R5") (pin "2") (pinfunction "2_2") (pintype "passive"))
    )
    (net (code "99") (name "Net-(IC5-INA)") (class "Default")
      (node (ref "IC5") (pin "3") (pinfunction "INA_3") (pintype "passive"))
      (node (ref "R6") (pin "2") (pinfunction "2_2") (pintype "passive"))
    )
    (net (code "100") (name "Net-(IC5-OUTC)") (class "Default")
      (node (ref "IC5") (pin "5") (pinfunction "OUTC_5") (pintype "passive"))
      (node (ref "R7") (pin "2") (pinfunction "2_2") (pintype "passive"))
    )
    (net (code "101") (name "Net-(IC5-OUTD)") (class "Default")
      (node (ref "IC5") (pin "6") (pinfunction "OUTD_6") (pintype "passive"))
      (node (ref "R8") (pin "2") (pinfunction "2_2") (pintype "passive"))
    )
    (net (code "102") (name "VDD_UNREG_12V") (class "Default")
      (node (ref "D18") (pin "2") (pinfunction "C_2") (pintype "passive"))
      (node (ref "J17") (pin "1") (pinfunction "1_1") (pintype "passive"))
      (node (ref "J8") (pin "1") (pinfunction "1_1") (pintype "passive"))
      (node (ref "TP11") (pin "1") (pinfunction "1_1") (pintype "passive"))
    )
    (net (code "103") (name "VDD_UNREG_HB") (class "Default")
      (node (ref "D17") (pin "2") (pinfunction "C_2") (pintype "passive"))
      (node (ref "J15") (pin "1") (pinfunction "1_1") (pintype "passive"))
      (node (ref "J6") (pin "1") (pinfunction "1_1") (pintype "passive"))
      (node (ref "TP8") (pin "1") (pinfunction "1_1") (pintype "passive"))
    )
    (net (code "104") (name "VIN") (class "Default")
      (node (ref "J1") (pin "1") (pinfunction "1_1") (pintype "passive"))
      (node (ref "J2") (pin "1") (pinfunction "1_1") (pintype "passive"))
      (node (ref "TP1") (pin "1") (pinfunction "1_1") (pintype "passive"))
    )
    (net (code "105") (name "unconnected-(IC4-NC-Pad7)") (class "Default")
      (node (ref "IC4") (pin "7") (pinfunction "NC_7") (pintype "passive+no_connect"))
    )
    (net (code "106") (name "unconnected-(IC5-INB-Pad4)") (class "Default")
      (node (ref "IC5") (pin "4") (pinfunction "INB_4") (pintype "passive+no_connect"))
    )
    (net (code "107") (name "unconnected-(IC5-OUTB-Pad13)") (class "Default")
      (node (ref "IC5") (pin "13") (pinfunction "OUTB_13") (pintype "passive+no_connect"))
    )
  )
)
